# esp-4relay-board.net
KiCad netlist of a schematic drawn in EAGLE
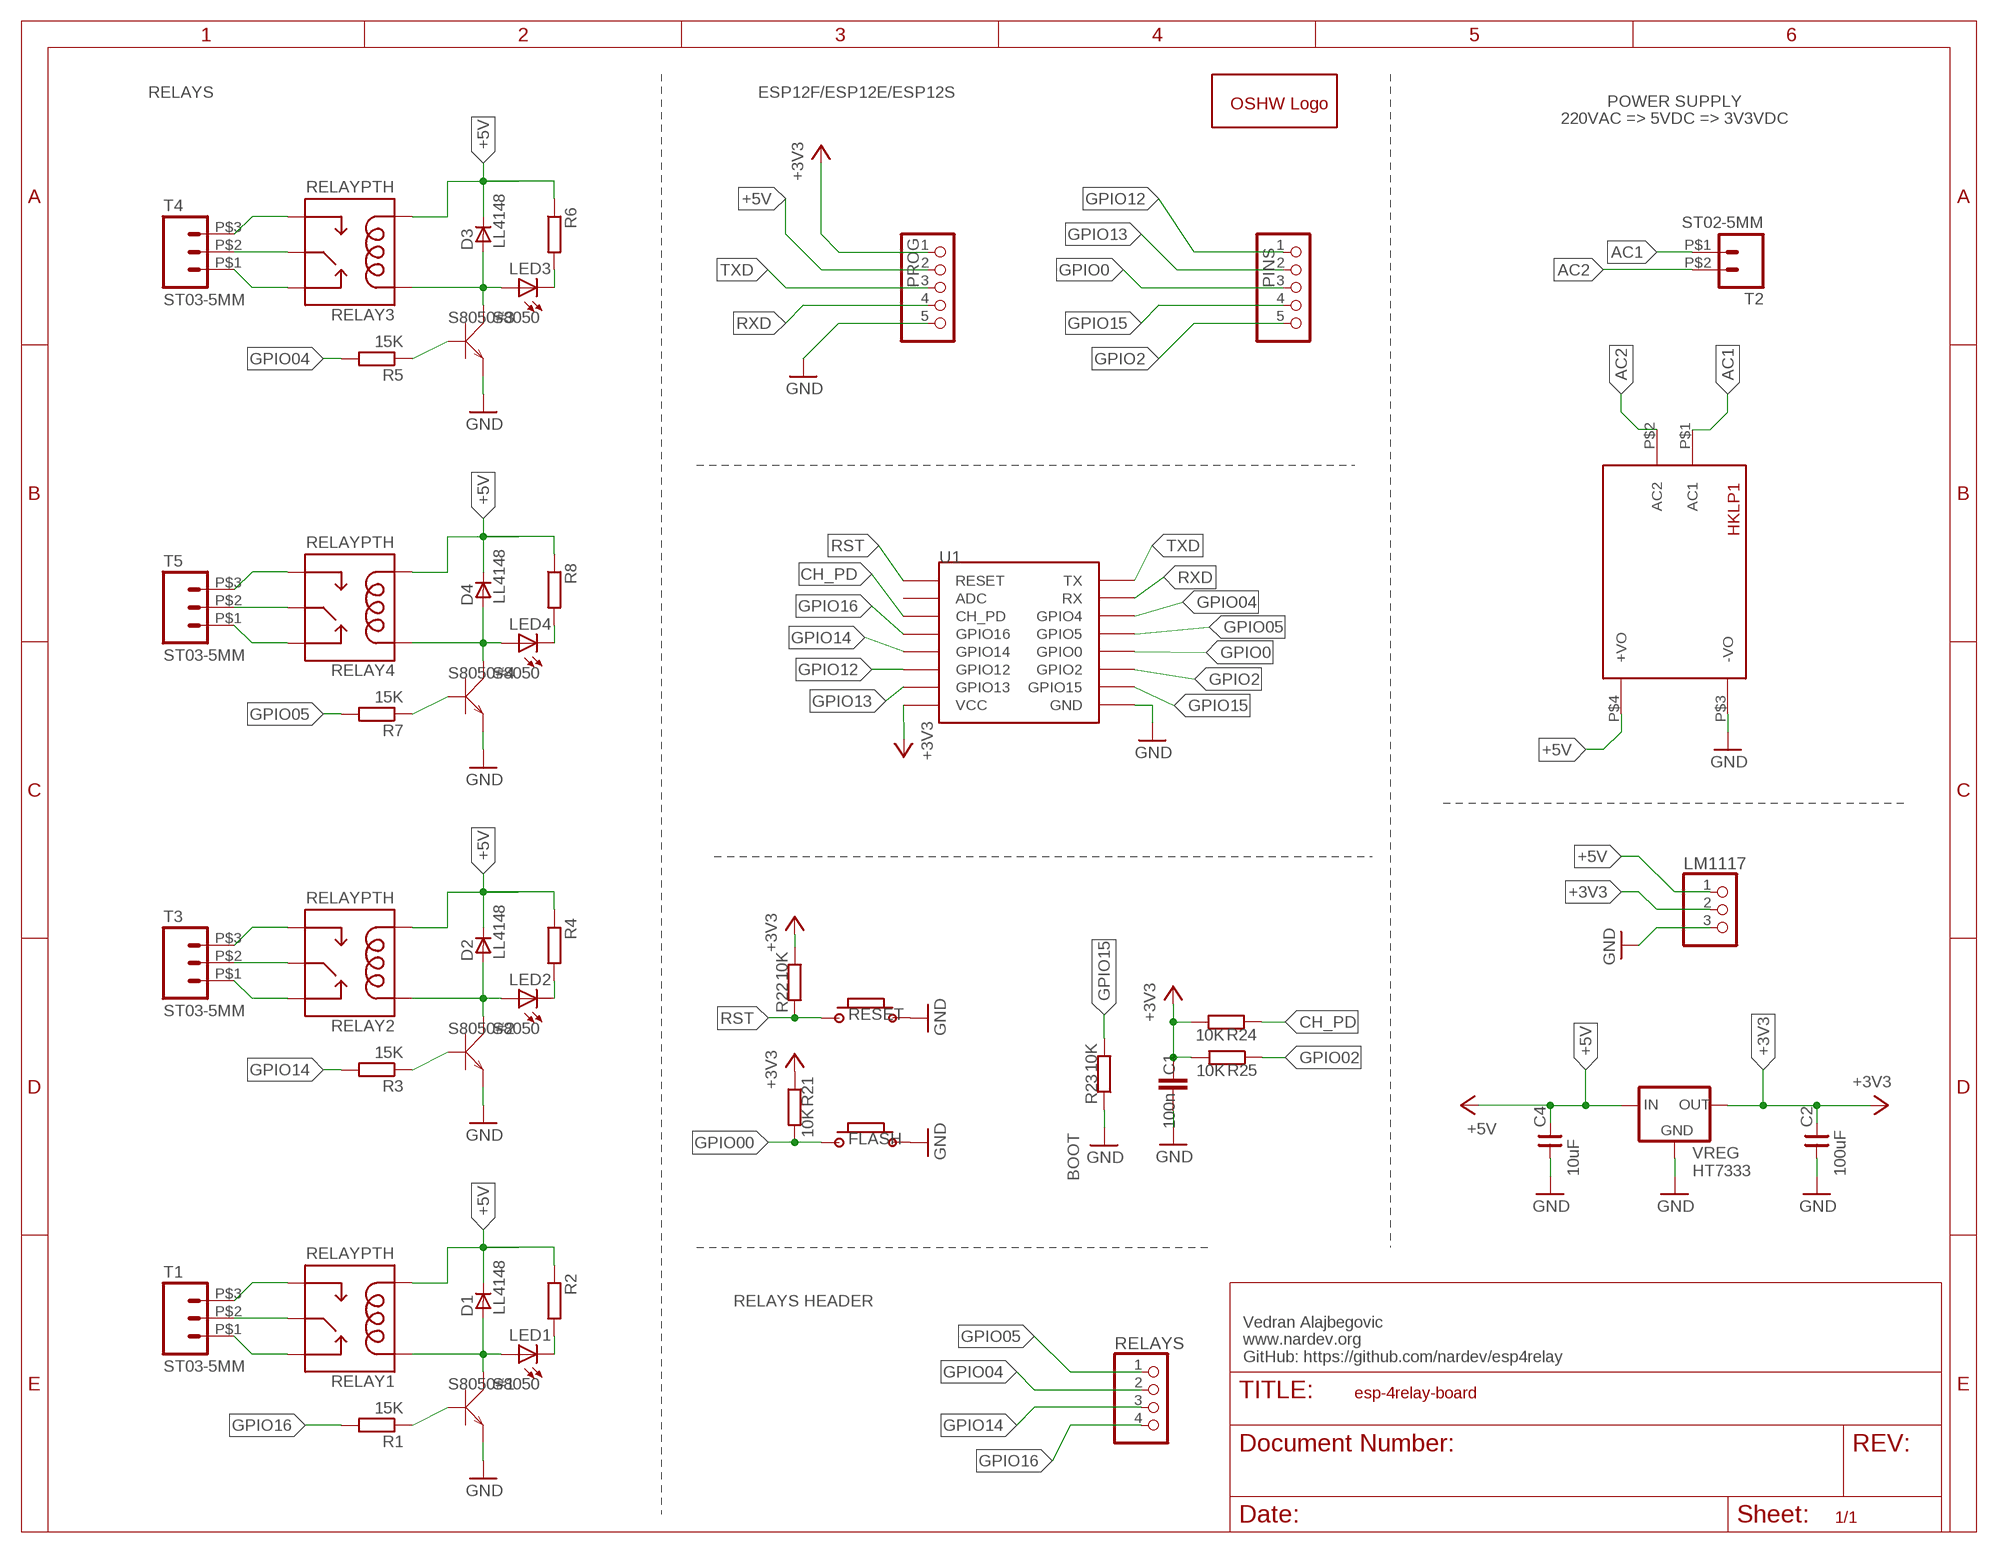
[diagram p0: schematic, sheet 1]

(export (version "E")
  (design (tool "Eeschema 10.0.6"))
  (components
    (comp (ref "C1")
      (value "100n")
      (footprint "eagle-import:C_0805")
      (libsource (lib "eagle-import") (part "CAPC0805"))
    )
    (comp (ref "C2")
      (value "100uF")
      (footprint "eagle-import:3216")
      (libsource (lib "eagle-import") (part "CNP-3216"))
    )
    (comp (ref "C4")
      (value "10uF")
      (footprint "eagle-import:3216")
      (libsource (lib "eagle-import") (part "CNP-3216"))
    )
    (comp (ref "D1")
      (value "LL4148")
      (footprint "eagle-import:SOD80_DO213AA_MINIMELF")
      (libsource (lib "eagle-import") (part "LL4148"))
    )
    (comp (ref "D2")
      (value "LL4148")
      (footprint "eagle-import:SOD80_DO213AA_MINIMELF")
      (libsource (lib "eagle-import") (part "LL4148"))
    )
    (comp (ref "D3")
      (value "LL4148")
      (footprint "eagle-import:SOD80_DO213AA_MINIMELF")
      (libsource (lib "eagle-import") (part "LL4148"))
    )
    (comp (ref "D4")
      (value "LL4148")
      (footprint "eagle-import:SOD80_DO213AA_MINIMELF")
      (libsource (lib "eagle-import") (part "LL4148"))
    )
    (comp (ref "FLASH")
      (value "BUTTON-2PSWITCH-TURTLE-2P")
      (footprint "eagle-import:2P-SWITCH-TURTLE")
      (libsource (lib "eagle-import") (part "BUTTON-2PSWITCH-TURTLE-2P"))
    )
    (comp (ref "GOLD_ORB_SM1")
      (value "OSHWLOGOLOGO16MM")
      (footprint "eagle-import:OSHW_16MM")
      (libsource (lib "eagle-import") (part "OSHWLOGOLOGO16MM"))
    )
    (comp (ref "HKLP1")
      (value "HKLPM01")
      (footprint "eagle-import:HKLPM01")
      (libsource (lib "eagle-import") (part "HKLPM01"))
    )
    (comp (ref "LED1")
      (value "LEDSML0805")
      (footprint "eagle-import:SML0805")
      (libsource (lib "eagle-import") (part "LEDSML0805"))
    )
    (comp (ref "LED2")
      (value "LEDSML0805")
      (footprint "eagle-import:SML0805")
      (libsource (lib "eagle-import") (part "LEDSML0805"))
    )
    (comp (ref "LED3")
      (value "LEDSML0805")
      (footprint "eagle-import:SML0805")
      (libsource (lib "eagle-import") (part "LEDSML0805"))
    )
    (comp (ref "LED4")
      (value "LEDSML0805")
      (footprint "eagle-import:SML0805")
      (libsource (lib "eagle-import") (part "LEDSML0805"))
    )
    (comp (ref "LM1117")
      (value "PINHD-1X3")
      (footprint "eagle-import:1X03")
      (libsource (lib "eagle-import") (part "PINHD-1X3"))
    )
    (comp (ref "PINS")
      (value "PINHD-1X5")
      (footprint "eagle-import:1X05")
      (libsource (lib "eagle-import") (part "PINHD-1X5"))
    )
    (comp (ref "PROG")
      (value "PINHD-1X5")
      (footprint "eagle-import:1X05")
      (libsource (lib "eagle-import") (part "PINHD-1X5"))
    )
    (comp (ref "R1")
      (value "15K")
      (footprint "eagle-import:R1206")
      (libsource (lib "eagle-import") (part "R-EU_R1206"))
    )
    (comp (ref "R2")
      (value "R-EU_R1206")
      (footprint "eagle-import:R1206")
      (libsource (lib "eagle-import") (part "R-EU_R1206"))
    )
    (comp (ref "R3")
      (value "15K")
      (footprint "eagle-import:R1206")
      (libsource (lib "eagle-import") (part "R-EU_R1206"))
    )
    (comp (ref "R4")
      (value "R-EU_R1206")
      (footprint "eagle-import:R1206")
      (libsource (lib "eagle-import") (part "R-EU_R1206"))
    )
    (comp (ref "R5")
      (value "15K")
      (footprint "eagle-import:R1206")
      (libsource (lib "eagle-import") (part "R-EU_R1206"))
    )
    (comp (ref "R6")
      (value "R-EU_R1206")
      (footprint "eagle-import:R1206")
      (libsource (lib "eagle-import") (part "R-EU_R1206"))
    )
    (comp (ref "R7")
      (value "15K")
      (footprint "eagle-import:R1206")
      (libsource (lib "eagle-import") (part "R-EU_R1206"))
    )
    (comp (ref "R8")
      (value "R-EU_R1206")
      (footprint "eagle-import:R1206")
      (libsource (lib "eagle-import") (part "R-EU_R1206"))
    )
    (comp (ref "R21")
      (value "10K")
      (footprint "eagle-import:R_0805")
      (libsource (lib "eagle-import") (part "RESISTORR0805"))
    )
    (comp (ref "R22")
      (value "10K")
      (footprint "eagle-import:R_0805")
      (libsource (lib "eagle-import") (part "RESISTORR0805"))
    )
    (comp (ref "R23")
      (value "10K")
      (footprint "eagle-import:R_0805")
      (libsource (lib "eagle-import") (part "RESISTORR0805"))
    )
    (comp (ref "R24")
      (value "10K")
      (footprint "eagle-import:R_0805")
      (libsource (lib "eagle-import") (part "RESISTORR0805"))
    )
    (comp (ref "R25")
      (value "10K")
      (footprint "eagle-import:R_0805")
      (libsource (lib "eagle-import") (part "RESISTORR0805"))
    )
    (comp (ref "RELAY1")
      (value "RELAYPTH")
      (footprint "eagle-import:SRD-05VDC-SL-C")
      (libsource (lib "eagle-import") (part "RELAYPTH"))
    )
    (comp (ref "RELAY2")
      (value "RELAYPTH")
      (footprint "eagle-import:SRD-05VDC-SL-C")
      (libsource (lib "eagle-import") (part "RELAYPTH"))
    )
    (comp (ref "RELAY3")
      (value "RELAYPTH")
      (footprint "eagle-import:SRD-05VDC-SL-C")
      (libsource (lib "eagle-import") (part "RELAYPTH"))
    )
    (comp (ref "RELAY4")
      (value "RELAYPTH")
      (footprint "eagle-import:SRD-05VDC-SL-C")
      (libsource (lib "eagle-import") (part "RELAYPTH"))
    )
    (comp (ref "RELAYS")
      (value "PINHD-1X4")
      (footprint "eagle-import:1X04")
      (libsource (lib "eagle-import") (part "PINHD-1X4"))
    )
    (comp (ref "RESET")
      (value "BUTTON-2PSWITCH-TURTLE-2P")
      (footprint "eagle-import:2P-SWITCH-TURTLE")
      (libsource (lib "eagle-import") (part "BUTTON-2PSWITCH-TURTLE-2P"))
    )
    (comp (ref "S8050#1")
      (value "S8050")
      (footprint "eagle-import:SOT-23")
      (libsource (lib "eagle-import") (part "SMD-TRANSISTORS-NPN-25V-500MW-S8050(SOT-23)"))
    )
    (comp (ref "S8050#2")
      (value "S8050")
      (footprint "eagle-import:SOT-23")
      (libsource (lib "eagle-import") (part "SMD-TRANSISTORS-NPN-25V-500MW-S8050(SOT-23)"))
    )
    (comp (ref "S8050#3")
      (value "S8050")
      (footprint "eagle-import:SOT-23")
      (libsource (lib "eagle-import") (part "SMD-TRANSISTORS-NPN-25V-500MW-S8050(SOT-23)"))
    )
    (comp (ref "S8050#4")
      (value "S8050")
      (footprint "eagle-import:SOT-23")
      (libsource (lib "eagle-import") (part "SMD-TRANSISTORS-NPN-25V-500MW-S8050(SOT-23)"))
    )
    (comp (ref "T1")
      (value "ST03-5MM")
      (footprint "eagle-import:EK500V-03P")
      (libsource (lib "eagle-import") (part "ST03-5MM"))
    )
    (comp (ref "T2")
      (value "ST02-5MM")
      (footprint "eagle-import:EK500V-02P")
      (libsource (lib "eagle-import") (part "ST02-5MM"))
    )
    (comp (ref "T3")
      (value "ST03-5MM")
      (footprint "eagle-import:EK500V-03P")
      (libsource (lib "eagle-import") (part "ST03-5MM"))
    )
    (comp (ref "T4")
      (value "ST03-5MM")
      (footprint "eagle-import:EK500V-03P")
      (libsource (lib "eagle-import") (part "ST03-5MM"))
    )
    (comp (ref "T5")
      (value "ST03-5MM")
      (footprint "eagle-import:EK500V-03P")
      (libsource (lib "eagle-import") (part "ST03-5MM"))
    )
    (comp (ref "U1")
      (value "ESP12SMD")
      (footprint "eagle-import:ESP12-SMD")
      (libsource (lib "eagle-import") (part "ESP12SMD"))
    )
    (comp (ref "VREG")
      (value "HT7333")
      (footprint "eagle-import:SOT-89")
      (libsource (lib "eagle-import") (part "HT7333"))
    )
  )
  (nets
    (net (code "1") (name "+3V3") (class "Default")
      (node (ref "C1") (pin "1") (pinfunction "1_1") (pintype "passive"))
      (node (ref "C2") (pin "2") (pinfunction "2_2") (pintype "passive"))
      (node (ref "LM1117") (pin "2") (pinfunction "2_2") (pintype "passive"))
      (node (ref "PROG") (pin "1") (pinfunction "1_1") (pintype "passive"))
      (node (ref "R21") (pin "1") (pinfunction "1_1") (pintype "passive"))
      (node (ref "R22") (pin "2") (pinfunction "2_2") (pintype "passive"))
      (node (ref "R24") (pin "2") (pinfunction "2_2") (pintype "passive"))
      (node (ref "R25") (pin "2") (pinfunction "2_2") (pintype "passive"))
      (node (ref "U1") (pin "VCC") (pinfunction "VCC_VCC") (pintype "bidirectional"))
      (node (ref "VREG") (pin "1") (pinfunction "OUT_1") (pintype "passive"))
    )
    (net (code "2") (name "+5V") (class "Default")
      (node (ref "C4") (pin "2") (pinfunction "2_2") (pintype "passive"))
      (node (ref "D1") (pin "C") (pinfunction "C_C") (pintype "passive"))
      (node (ref "D2") (pin "C") (pinfunction "C_C") (pintype "passive"))
      (node (ref "D3") (pin "C") (pinfunction "C_C") (pintype "passive"))
      (node (ref "D4") (pin "C") (pinfunction "C_C") (pintype "passive"))
      (node (ref "HKLP1") (pin "P$4") (pinfunction "+VO_P$4") (pintype "bidirectional"))
      (node (ref "LM1117") (pin "1") (pinfunction "1_1") (pintype "passive"))
      (node (ref "PROG") (pin "2") (pinfunction "2_2") (pintype "passive"))
      (node (ref "R2") (pin "1") (pinfunction "1_1") (pintype "passive"))
      (node (ref "R4") (pin "1") (pinfunction "1_1") (pintype "passive"))
      (node (ref "R6") (pin "1") (pinfunction "1_1") (pintype "passive"))
      (node (ref "R8") (pin "1") (pinfunction "1_1") (pintype "passive"))
      (node (ref "RELAY1") (pin "COIL0") (pinfunction "COIL0_COIL0") (pintype "bidirectional"))
      (node (ref "RELAY2") (pin "COIL0") (pinfunction "COIL0_COIL0") (pintype "bidirectional"))
      (node (ref "RELAY3") (pin "COIL0") (pinfunction "COIL0_COIL0") (pintype "bidirectional"))
      (node (ref "RELAY4") (pin "COIL0") (pinfunction "COIL0_COIL0") (pintype "bidirectional"))
      (node (ref "VREG") (pin "3") (pinfunction "IN_3") (pintype "input"))
      (node (ref "VREG") (pin "4") (pinfunction "IN_4") (pintype "input"))
    )
    (net (code "3") (name "AC1") (class "Default")
      (node (ref "HKLP1") (pin "P$1") (pinfunction "AC1_P$1") (pintype "bidirectional"))
      (node (ref "T2") (pin "P$1") (pinfunction "1_P$1") (pintype "passive"))
    )
    (net (code "4") (name "AC2") (class "Default")
      (node (ref "HKLP1") (pin "P$2") (pinfunction "AC2_P$2") (pintype "bidirectional"))
      (node (ref "T2") (pin "P$2") (pinfunction "2_P$2") (pintype "passive"))
    )
    (net (code "5") (name "CH_PD") (class "Default")
      (node (ref "R24") (pin "1") (pinfunction "1_1") (pintype "passive"))
      (node (ref "U1") (pin "CH_PD") (pinfunction "CH_PD_CH_PD") (pintype "bidirectional"))
    )
    (net (code "6") (name "GND") (class "Default")
      (node (ref "C1") (pin "2") (pinfunction "2_2") (pintype "passive"))
      (node (ref "C2") (pin "1") (pinfunction "1_1") (pintype "passive"))
      (node (ref "C4") (pin "1") (pinfunction "1_1") (pintype "passive"))
      (node (ref "FLASH") (pin "2") (pinfunction "P$2_2") (pintype "bidirectional"))
      (node (ref "HKLP1") (pin "P$3") (pinfunction "-VO_P$3") (pintype "bidirectional"))
      (node (ref "LM1117") (pin "3") (pinfunction "3_3") (pintype "passive"))
      (node (ref "PROG") (pin "5") (pinfunction "5_5") (pintype "passive"))
      (node (ref "R23") (pin "1") (pinfunction "1_1") (pintype "passive"))
      (node (ref "RESET") (pin "2") (pinfunction "P$2_2") (pintype "bidirectional"))
      (node (ref "S8050#1") (pin "2") (pinfunction "E_2") (pintype "passive"))
      (node (ref "S8050#2") (pin "2") (pinfunction "E_2") (pintype "passive"))
      (node (ref "S8050#3") (pin "2") (pinfunction "E_2") (pintype "passive"))
      (node (ref "S8050#4") (pin "2") (pinfunction "E_2") (pintype "passive"))
      (node (ref "U1") (pin "GND") (pinfunction "GND_GND") (pintype "bidirectional"))
      (node (ref "VREG") (pin "2") (pinfunction "GND_2") (pintype "input"))
    )
    (net (code "7") (name "GPIO00") (class "Default")
      (node (ref "FLASH") (pin "1") (pinfunction "P$1_1") (pintype "bidirectional"))
      (node (ref "R21") (pin "2") (pinfunction "2_2") (pintype "passive"))
    )
    (net (code "8") (name "GPIO0") (class "Default")
      (node (ref "PINS") (pin "3") (pinfunction "3_3") (pintype "passive"))
      (node (ref "U1") (pin "GPIO0") (pinfunction "GPIO0_GPIO0") (pintype "bidirectional"))
    )
    (net (code "9") (name "GPIO2") (class "Default")
      (node (ref "PINS") (pin "5") (pinfunction "5_5") (pintype "passive"))
      (node (ref "U1") (pin "GPIO2") (pinfunction "GPIO2_GPIO2") (pintype "bidirectional"))
    )
    (net (code "10") (name "GPIO02") (class "Default")
      (node (ref "R25") (pin "1") (pinfunction "1_1") (pintype "passive"))
    )
    (net (code "11") (name "GPIO04") (class "Default")
      (node (ref "R5") (pin "2") (pinfunction "2_2") (pintype "passive"))
      (node (ref "RELAYS") (pin "2") (pinfunction "2_2") (pintype "passive"))
      (node (ref "U1") (pin "GPIO4") (pinfunction "GPIO4_GPIO4") (pintype "bidirectional"))
    )
    (net (code "12") (name "GPIO05") (class "Default")
      (node (ref "R7") (pin "2") (pinfunction "2_2") (pintype "passive"))
      (node (ref "RELAYS") (pin "1") (pinfunction "1_1") (pintype "passive"))
      (node (ref "U1") (pin "GPIO5") (pinfunction "GPIO5_GPIO5") (pintype "bidirectional"))
    )
    (net (code "13") (name "GPIO12") (class "Default")
      (node (ref "PINS") (pin "1") (pinfunction "1_1") (pintype "passive"))
      (node (ref "U1") (pin "GPIO12") (pinfunction "GPIO12_GPIO12") (pintype "bidirectional"))
    )
    (net (code "14") (name "GPIO13") (class "Default")
      (node (ref "PINS") (pin "2") (pinfunction "2_2") (pintype "passive"))
      (node (ref "U1") (pin "GPIO13") (pinfunction "GPIO13_GPIO13") (pintype "bidirectional"))
    )
    (net (code "15") (name "GPIO14") (class "Default")
      (node (ref "R3") (pin "2") (pinfunction "2_2") (pintype "passive"))
      (node (ref "RELAYS") (pin "3") (pinfunction "3_3") (pintype "passive"))
      (node (ref "U1") (pin "GPIO14") (pinfunction "GPIO14_GPIO14") (pintype "bidirectional"))
    )
    (net (code "16") (name "GPIO15") (class "Default")
      (node (ref "PINS") (pin "4") (pinfunction "4_4") (pintype "passive"))
      (node (ref "R23") (pin "2") (pinfunction "2_2") (pintype "passive"))
      (node (ref "U1") (pin "GPIO15") (pinfunction "GPIO15_GPIO15") (pintype "bidirectional"))
    )
    (net (code "17") (name "GPIO16") (class "Default")
      (node (ref "R1") (pin "2") (pinfunction "2_2") (pintype "passive"))
      (node (ref "RELAYS") (pin "4") (pinfunction "4_4") (pintype "passive"))
      (node (ref "U1") (pin "GPIO16") (pinfunction "GPIO16_GPIO16") (pintype "bidirectional"))
    )
    (net (code "18") (name "Net-(LED1-PadC)") (class "Default")
      (node (ref "LED1") (pin "C") (pinfunction "C_C") (pintype "passive"))
      (node (ref "R2") (pin "2") (pinfunction "2_2") (pintype "passive"))
    )
    (net (code "19") (name "Net-(LED2-PadC)") (class "Default")
      (node (ref "LED2") (pin "C") (pinfunction "C_C") (pintype "passive"))
      (node (ref "R4") (pin "2") (pinfunction "2_2") (pintype "passive"))
    )
    (net (code "20") (name "Net-(LED3-PadC)") (class "Default")
      (node (ref "LED3") (pin "C") (pinfunction "C_C") (pintype "passive"))
      (node (ref "R6") (pin "2") (pinfunction "2_2") (pintype "passive"))
    )
    (net (code "21") (name "Net-(LED4-PadC)") (class "Default")
      (node (ref "LED4") (pin "C") (pinfunction "C_C") (pintype "passive"))
      (node (ref "R8") (pin "2") (pinfunction "2_2") (pintype "passive"))
    )
    (net (code "22") (name "Net-(RELAY1-SWCLOSE)") (class "Default")
      (node (ref "RELAY1") (pin "SWCLOSED") (pinfunction "SWCLOSE_SWCLOSED") (pintype "bidirectional"))
      (node (ref "T1") (pin "P$1") (pinfunction "1_P$1") (pintype "passive"))
    )
    (net (code "23") (name "Net-(RELAY2-SWCLOSE)") (class "Default")
      (node (ref "RELAY2") (pin "SWCLOSED") (pinfunction "SWCLOSE_SWCLOSED") (pintype "bidirectional"))
      (node (ref "T3") (pin "P$1") (pinfunction "1_P$1") (pintype "passive"))
    )
    (net (code "24") (name "Net-(RELAY3-SWCLOSE)") (class "Default")
      (node (ref "RELAY3") (pin "SWCLOSED") (pinfunction "SWCLOSE_SWCLOSED") (pintype "bidirectional"))
      (node (ref "T4") (pin "P$1") (pinfunction "1_P$1") (pintype "passive"))
    )
    (net (code "25") (name "Net-(RELAY4-SWCLOSE)") (class "Default")
      (node (ref "RELAY4") (pin "SWCLOSED") (pinfunction "SWCLOSE_SWCLOSED") (pintype "bidirectional"))
      (node (ref "T5") (pin "P$1") (pinfunction "1_P$1") (pintype "passive"))
    )
    (net (code "26") (name "Net-(S8050#1-B)") (class "Default")
      (node (ref "R1") (pin "1") (pinfunction "1_1") (pintype "passive"))
      (node (ref "S8050#1") (pin "1") (pinfunction "B_1") (pintype "passive"))
    )
    (net (code "27") (name "Net-(S8050#1-C)") (class "Default")
      (node (ref "D1") (pin "A") (pinfunction "A_A") (pintype "passive"))
      (node (ref "LED1") (pin "A") (pinfunction "A_A") (pintype "passive"))
      (node (ref "RELAY1") (pin "COIL1") (pinfunction "COIL1_COIL1") (pintype "bidirectional"))
      (node (ref "S8050#1") (pin "3") (pinfunction "C_3") (pintype "passive"))
    )
    (net (code "28") (name "Net-(S8050#2-B)") (class "Default")
      (node (ref "R3") (pin "1") (pinfunction "1_1") (pintype "passive"))
      (node (ref "S8050#2") (pin "1") (pinfunction "B_1") (pintype "passive"))
    )
    (net (code "29") (name "Net-(S8050#2-C)") (class "Default")
      (node (ref "D2") (pin "A") (pinfunction "A_A") (pintype "passive"))
      (node (ref "LED2") (pin "A") (pinfunction "A_A") (pintype "passive"))
      (node (ref "RELAY2") (pin "COIL1") (pinfunction "COIL1_COIL1") (pintype "bidirectional"))
      (node (ref "S8050#2") (pin "3") (pinfunction "C_3") (pintype "passive"))
    )
    (net (code "30") (name "Net-(S8050#3-B)") (class "Default")
      (node (ref "R5") (pin "1") (pinfunction "1_1") (pintype "passive"))
      (node (ref "S8050#3") (pin "1") (pinfunction "B_1") (pintype "passive"))
    )
    (net (code "31") (name "Net-(S8050#3-C)") (class "Default")
      (node (ref "D3") (pin "A") (pinfunction "A_A") (pintype "passive"))
      (node (ref "LED3") (pin "A") (pinfunction "A_A") (pintype "passive"))
      (node (ref "RELAY3") (pin "COIL1") (pinfunction "COIL1_COIL1") (pintype "bidirectional"))
      (node (ref "S8050#3") (pin "3") (pinfunction "C_3") (pintype "passive"))
    )
    (net (code "32") (name "Net-(S8050#4-B)") (class "Default")
      (node (ref "R7") (pin "1") (pinfunction "1_1") (pintype "passive"))
      (node (ref "S8050#4") (pin "1") (pinfunction "B_1") (pintype "passive"))
    )
    (net (code "33") (name "Net-(S8050#4-C)") (class "Default")
      (node (ref "D4") (pin "A") (pinfunction "A_A") (pintype "passive"))
      (node (ref "LED4") (pin "A") (pinfunction "A_A") (pintype "passive"))
      (node (ref "RELAY4") (pin "COIL1") (pinfunction "COIL1_COIL1") (pintype "bidirectional"))
      (node (ref "S8050#4") (pin "3") (pinfunction "C_3") (pintype "passive"))
    )
    (net (code "34") (name "Net-(T1-2)") (class "Default")
      (node (ref "RELAY1") (pin "SWCOMMON") (pinfunction "SWCOMMON_SWCOMMON") (pintype "bidirectional"))
      (node (ref "T1") (pin "P$2") (pinfunction "2_P$2") (pintype "passive"))
    )
    (net (code "35") (name "Net-(T1-3)") (class "Default")
      (node (ref "RELAY1") (pin "SWOPEN") (pinfunction "SWOPEN_SWOPEN") (pintype "bidirectional"))
      (node (ref "T1") (pin "P$3") (pinfunction "3_P$3") (pintype "passive"))
    )
    (net (code "36") (name "Net-(T3-2)") (class "Default")
      (node (ref "RELAY2") (pin "SWCOMMON") (pinfunction "SWCOMMON_SWCOMMON") (pintype "bidirectional"))
      (node (ref "T3") (pin "P$2") (pinfunction "2_P$2") (pintype "passive"))
    )
    (net (code "37") (name "Net-(T3-3)") (class "Default")
      (node (ref "RELAY2") (pin "SWOPEN") (pinfunction "SWOPEN_SWOPEN") (pintype "bidirectional"))
      (node (ref "T3") (pin "P$3") (pinfunction "3_P$3") (pintype "passive"))
    )
    (net (code "38") (name "Net-(T4-2)") (class "Default")
      (node (ref "RELAY3") (pin "SWCOMMON") (pinfunction "SWCOMMON_SWCOMMON") (pintype "bidirectional"))
      (node (ref "T4") (pin "P$2") (pinfunction "2_P$2") (pintype "passive"))
    )
    (net (code "39") (name "Net-(T4-3)") (class "Default")
      (node (ref "RELAY3") (pin "SWOPEN") (pinfunction "SWOPEN_SWOPEN") (pintype "bidirectional"))
      (node (ref "T4") (pin "P$3") (pinfunction "3_P$3") (pintype "passive"))
    )
    (net (code "40") (name "Net-(T5-2)") (class "Default")
      (node (ref "RELAY4") (pin "SWCOMMON") (pinfunction "SWCOMMON_SWCOMMON") (pintype "bidirectional"))
      (node (ref "T5") (pin "P$2") (pinfunction "2_P$2") (pintype "passive"))
    )
    (net (code "41") (name "Net-(T5-3)") (class "Default")
      (node (ref "RELAY4") (pin "SWOPEN") (pinfunction "SWOPEN_SWOPEN") (pintype "bidirectional"))
      (node (ref "T5") (pin "P$3") (pinfunction "3_P$3") (pintype "passive"))
    )
    (net (code "42") (name "RST") (class "Default")
      (node (ref "R22") (pin "1") (pinfunction "1_1") (pintype "passive"))
      (node (ref "RESET") (pin "1") (pinfunction "P$1_1") (pintype "bidirectional"))
      (node (ref "U1") (pin "RESET") (pinfunction "RESET_RESET") (pintype "bidirectional"))
    )
    (net (code "43") (name "RXD") (class "Default")
      (node (ref "PROG") (pin "4") (pinfunction "4_4") (pintype "passive"))
      (node (ref "U1") (pin "RXD0") (pinfunction "RX_RXD0") (pintype "bidirectional"))
    )
    (net (code "44") (name "TXD") (class "Default")
      (node (ref "PROG") (pin "3") (pinfunction "3_3") (pintype "passive"))
      (node (ref "U1") (pin "TXD0") (pinfunction "TX_TXD0") (pintype "bidirectional"))
    )
    (net (code "45") (name "unconnected-(U1-PadADC)") (class "Default")
      (node (ref "U1") (pin "ADC") (pinfunction "ADC_ADC") (pintype "bidirectional"))
    )
  )
)
